# SCH___2022-11-10.net
KiCad netlist of a schematic drawn in EasyEDA
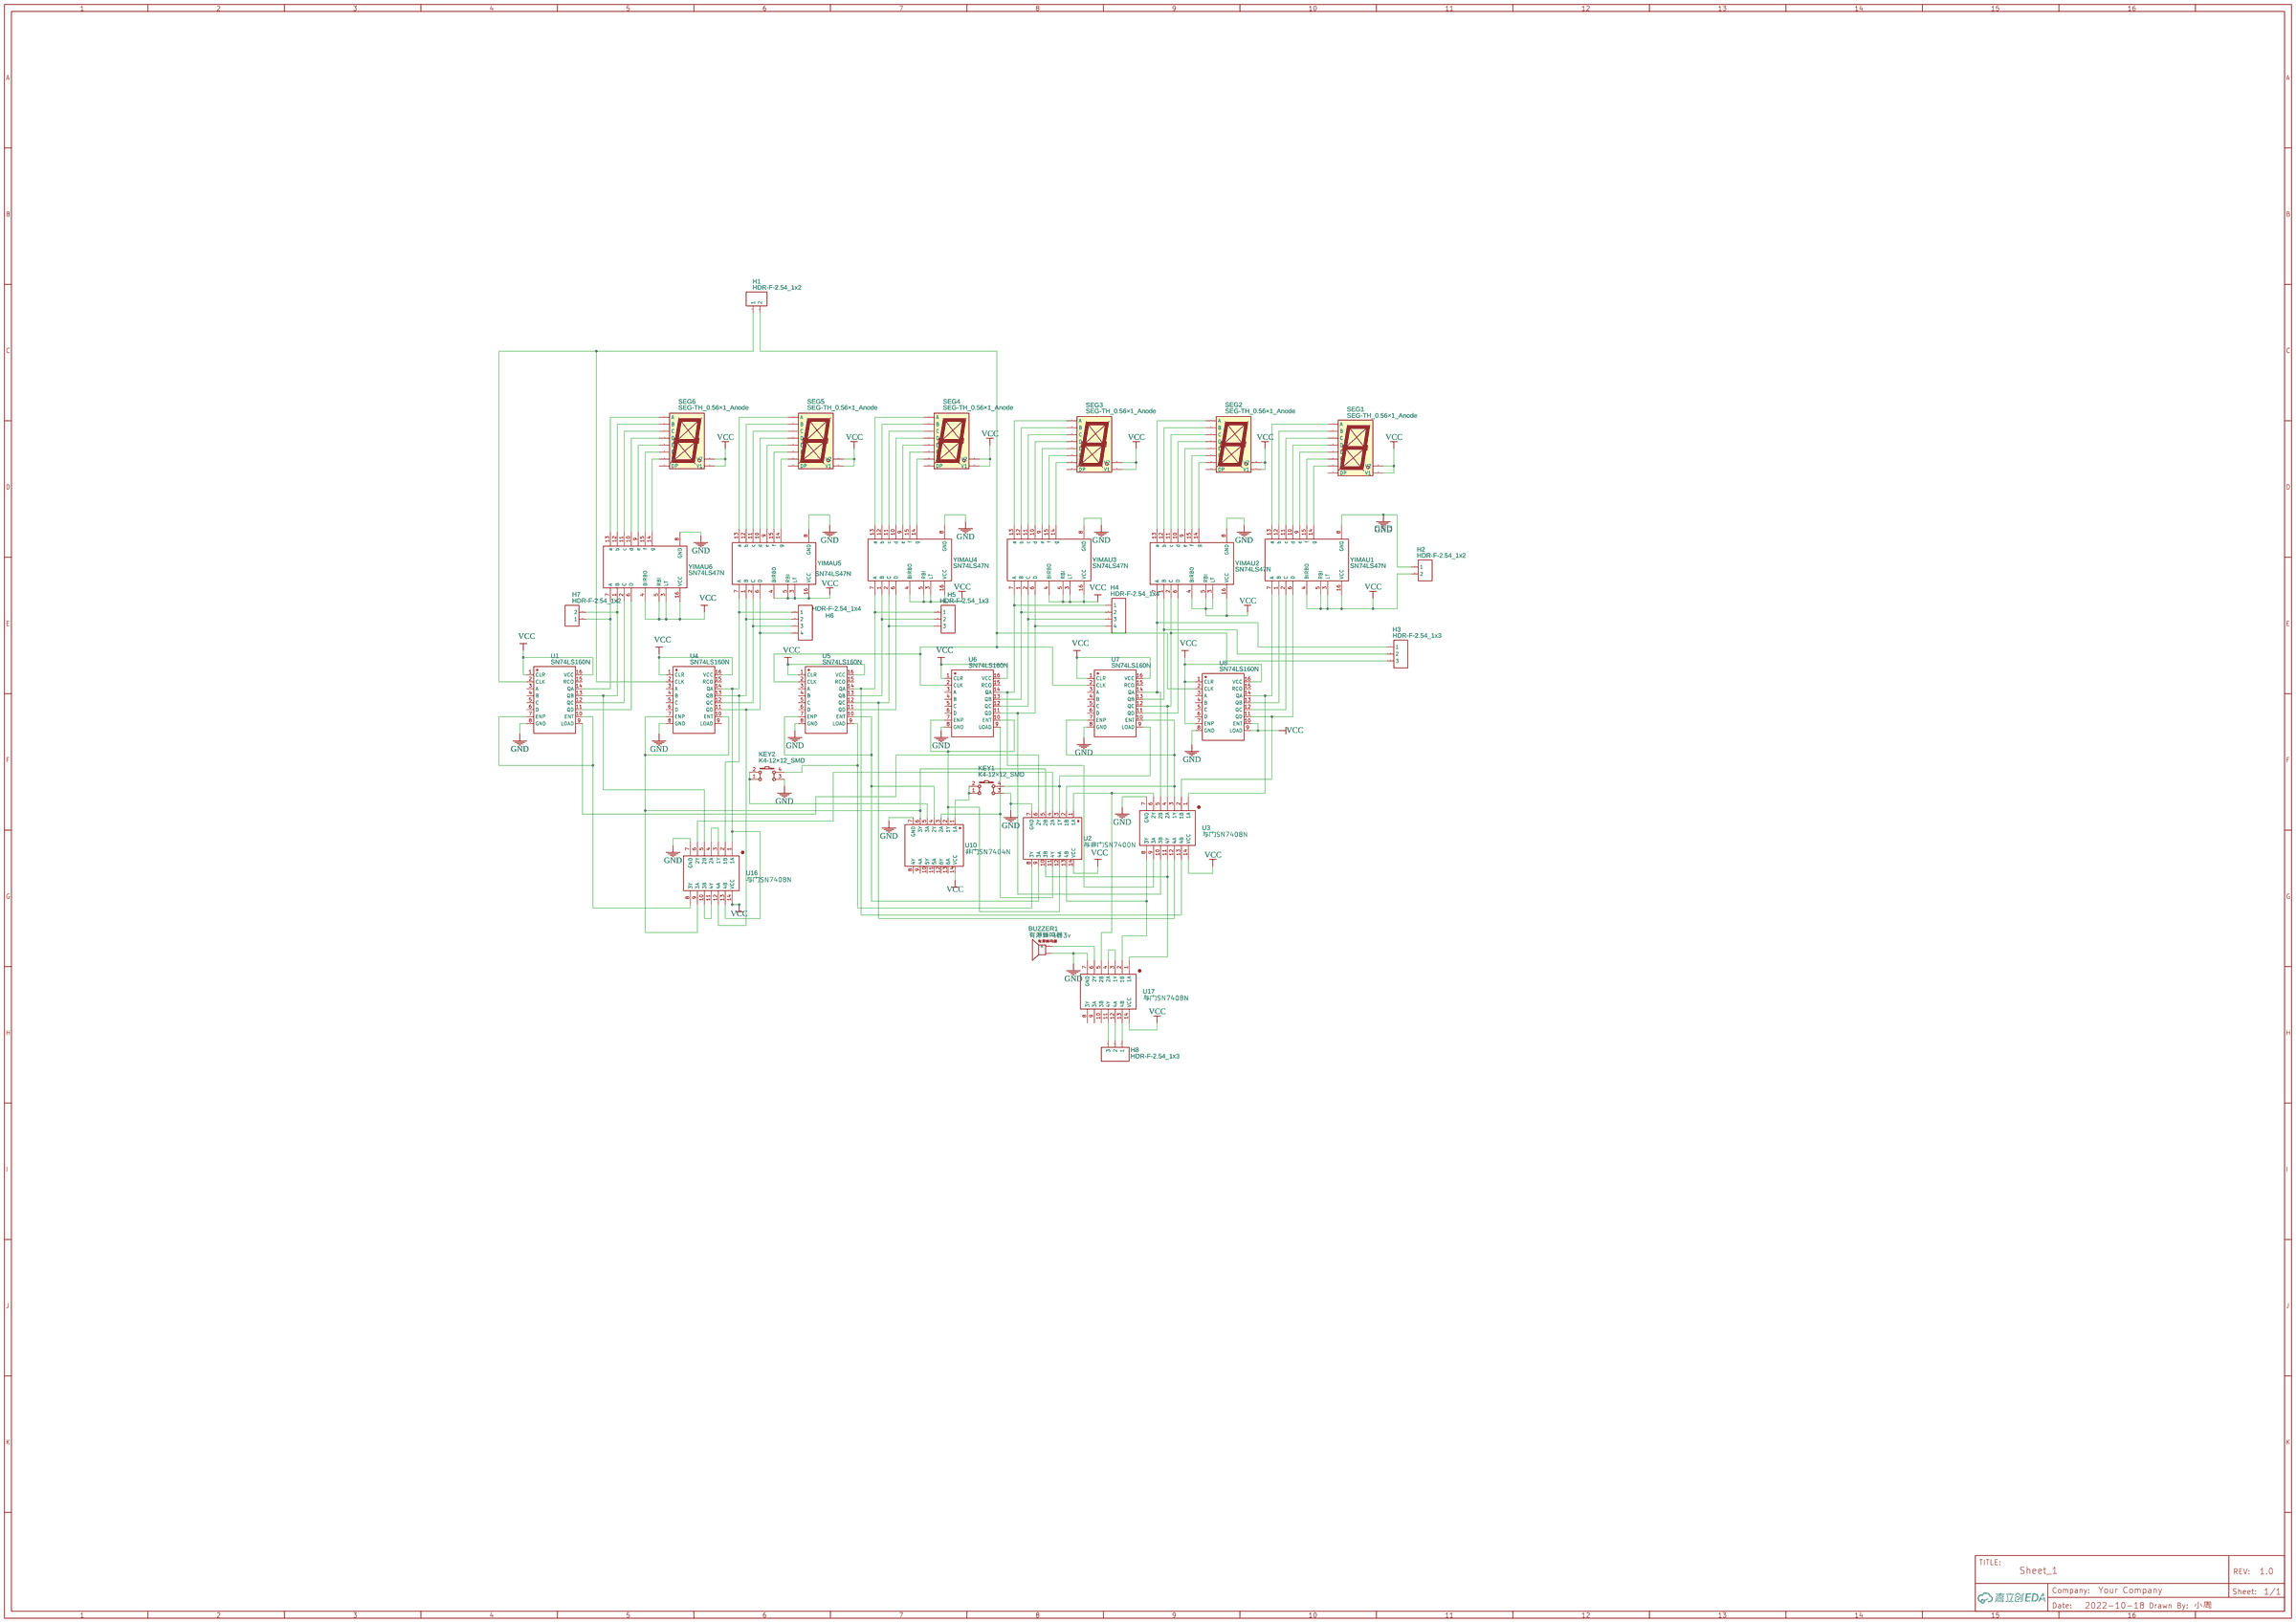
[diagram p0: schematic sheet]

(export (version "E")
  (design (tool "Eeschema 10.0.6"))
  (components
    (comp (ref "BUZZER1")
      (value "有源蜂鸣器3v")
      (fields (field (name "BOM_Manufacturer Part") "TMB12A12") (field (name "BOM_Supplier Part") "C96079"))
      (libsource (lib "") (part "有源蜂鸣器3v"))
    )
    (comp (ref "H1")
      (value "HDR-F-2.54_1x2")
      (fields (field (name "BOM_Supplier Part") "C49661"))
      (libsource (lib "") (part "HDR-F-2.54_1x2"))
    )
    (comp (ref "H2")
      (value "HDR-F-2.54_1x2")
      (fields (field (name "BOM_Supplier Part") "C49661"))
      (libsource (lib "") (part "HDR-F-2.54_1x2_2"))
    )
    (comp (ref "H3")
      (value "HDR-F-2.54_1x3")
      (fields (field (name "BOM_Supplier Part") "C146690"))
      (libsource (lib "") (part "HDR-F-2.54_1x3_1"))
    )
    (comp (ref "H4")
      (value "HDR-F-2.54_1x4")
      (fields (field (name "BOM_Supplier Part") "C225501"))
      (libsource (lib "") (part "HDR-F-2.54_1x4"))
    )
    (comp (ref "H5")
      (value "HDR-F-2.54_1x3")
      (fields (field (name "BOM_Supplier Part") "C146690"))
      (libsource (lib "") (part "HDR-F-2.54_1x3_1"))
    )
    (comp (ref "H6")
      (value "HDR-F-2.54_1x4")
      (fields (field (name "BOM_Supplier Part") "C225501"))
      (libsource (lib "") (part "HDR-F-2.54_1x4"))
    )
    (comp (ref "H7")
      (value "HDR-F-2.54_1x2")
      (fields (field (name "BOM_Supplier Part") "C49661"))
      (libsource (lib "") (part "HDR-F-2.54_1x2_1"))
    )
    (comp (ref "H8")
      (value "HDR-F-2.54_1x3")
      (fields (field (name "BOM_Supplier Part") "C146690"))
      (libsource (lib "") (part "HDR-F-2.54_1x3"))
    )
    (comp (ref "KEY1")
      (value "K4-12×12_SMD")
      (fields
        (field (name "BOM_Manufacturer Part") "K2-1103SP-E4SW-04")
        (field (name "BOM_Supplier Part") "C136697")
      )
      (libsource (lib "") (part "K4-12×12_SMD"))
    )
    (comp (ref "KEY2")
      (value "K4-12×12_SMD")
      (fields
        (field (name "BOM_Manufacturer Part") "K2-1103SP-E4SW-04")
        (field (name "BOM_Supplier Part") "C136697")
      )
      (libsource (lib "") (part "K4-12×12_SMD"))
    )
    (comp (ref "SEG1")
      (value "SEG-TH_0.56×1_Anode")
      (fields (field (name "BOM_Supplier Part") "C8092"))
      (libsource (lib "") (part "SEG-TH_0.56×1_Anode"))
    )
    (comp (ref "SEG2")
      (value "SEG-TH_0.56×1_Anode")
      (fields (field (name "BOM_Supplier Part") "C8092"))
      (libsource (lib "") (part "SEG-TH_0.56×1_Anode"))
    )
    (comp (ref "SEG3")
      (value "SEG-TH_0.56×1_Anode")
      (fields (field (name "BOM_Supplier Part") "C8092"))
      (libsource (lib "") (part "SEG-TH_0.56×1_Anode"))
    )
    (comp (ref "SEG4")
      (value "SEG-TH_0.56×1_Anode")
      (fields (field (name "BOM_Supplier Part") "C8092"))
      (libsource (lib "") (part "SEG-TH_0.56×1_Anode"))
    )
    (comp (ref "SEG5")
      (value "SEG-TH_0.56×1_Anode")
      (fields (field (name "BOM_Supplier Part") "C8092"))
      (libsource (lib "") (part "SEG-TH_0.56×1_Anode"))
    )
    (comp (ref "SEG6")
      (value "SEG-TH_0.56×1_Anode")
      (fields (field (name "BOM_Supplier Part") "C8092"))
      (libsource (lib "") (part "SEG-TH_0.56×1_Anode"))
    )
    (comp (ref "U1")
      (value "SN74LS160N")
      (fields
        (field (name "BOM_Manufacturer Part") "CC0805JRNPO9BN821")
        (field (name "BOM_Supplier Part") "C113834")
      )
      (libsource (lib "") (part "SN74LS160N"))
    )
    (comp (ref "U2") (value "与非门SN7400N") (libsource (lib "") (part "SN7400N")))
    (comp (ref "U3") (value "与门SN7408N") (libsource (lib "") (part "SN7408N")))
    (comp (ref "U4")
      (value "SN74LS160N")
      (fields
        (field (name "BOM_Manufacturer Part") "CC0805JRNPO9BN821")
        (field (name "BOM_Supplier Part") "C113834")
      )
      (libsource (lib "") (part "SN74LS160N"))
    )
    (comp (ref "U5")
      (value "SN74LS160N")
      (fields
        (field (name "BOM_Manufacturer Part") "CC0805JRNPO9BN821")
        (field (name "BOM_Supplier Part") "C113834")
      )
      (libsource (lib "") (part "SN74LS160N"))
    )
    (comp (ref "U6")
      (value "SN74LS160N")
      (fields
        (field (name "BOM_Manufacturer Part") "CC0805JRNPO9BN821")
        (field (name "BOM_Supplier Part") "C113834")
      )
      (libsource (lib "") (part "SN74LS160N"))
    )
    (comp (ref "U7")
      (value "SN74LS160N")
      (fields
        (field (name "BOM_Manufacturer Part") "CC0805JRNPO9BN821")
        (field (name "BOM_Supplier Part") "C113834")
      )
      (libsource (lib "") (part "SN74LS160N"))
    )
    (comp (ref "U8")
      (value "SN74LS160N")
      (fields
        (field (name "BOM_Manufacturer Part") "CC0805JRNPO9BN821")
        (field (name "BOM_Supplier Part") "C113834")
      )
      (libsource (lib "") (part "SN74LS160N"))
    )
    (comp (ref "U10") (value "非门SN7404N") (libsource (lib "") (part "SN7404N")))
    (comp (ref "U16") (value "与门SN7408N") (libsource (lib "") (part "SN7408N")))
    (comp (ref "U17") (value "与门SN7408N") (libsource (lib "") (part "SN7408N")))
    (comp (ref "YIMAU1")
      (value "SN74LS47N")
      (fields (field (name "BOM_Supplier Part") "C129379"))
      (libsource (lib "") (part "Unknown_1870_-1520"))
    )
    (comp (ref "YIMAU2")
      (value "SN74LS47N")
      (fields (field (name "BOM_Supplier Part") "C129379"))
      (libsource (lib "") (part "Unknown_1705_-1515"))
    )
    (comp (ref "YIMAU3")
      (value "SN74LS47N")
      (fields (field (name "BOM_Supplier Part") "C129379"))
      (libsource (lib "") (part "Unknown_1500_-1520"))
    )
    (comp (ref "YIMAU4")
      (value "SN74LS47N")
      (fields (field (name "BOM_Supplier Part") "C129379"))
      (libsource (lib "") (part "Unknown_1300_-1520"))
    )
    (comp (ref "YIMAU5")
      (value "SN74LS47N")
      (fields (field (name "BOM_Supplier Part") "C129379"))
      (libsource (lib "") (part "Unknown_1105_-1515"))
    )
    (comp (ref "YIMAU6")
      (value "SN74LS47N")
      (fields (field (name "BOM_Supplier Part") "C129379"))
      (libsource (lib "") (part "Unknown_920_-1510"))
    )
  )
  (nets
    (net (code "1") (name "GND") (class "Default")
      (node (ref "BUZZER1") (pin "-") (pinfunction "-_-") (pintype "unspecified"))
      (node (ref "H2") (pin "1") (pinfunction "1_1") (pintype "input"))
      (node (ref "KEY1") (pin "3") (pinfunction "3_3") (pintype "unspecified"))
      (node (ref "KEY2") (pin "3") (pinfunction "3_3") (pintype "unspecified"))
      (node (ref "U1") (pin "8") (pinfunction "GND_8") (pintype "unspecified"))
      (node (ref "U10") (pin "7") (pinfunction "GND_7") (pintype "unspecified"))
      (node (ref "U16") (pin "7") (pinfunction "GND_7") (pintype "unspecified"))
      (node (ref "U17") (pin "7") (pinfunction "GND_7") (pintype "unspecified"))
      (node (ref "U2") (pin "7") (pinfunction "GND_7") (pintype "unspecified"))
      (node (ref "U3") (pin "7") (pinfunction "GND_7") (pintype "unspecified"))
      (node (ref "U4") (pin "8") (pinfunction "GND_8") (pintype "unspecified"))
      (node (ref "U5") (pin "8") (pinfunction "GND_8") (pintype "unspecified"))
      (node (ref "U6") (pin "8") (pinfunction "GND_8") (pintype "unspecified"))
      (node (ref "U7") (pin "8") (pinfunction "GND_8") (pintype "unspecified"))
      (node (ref "U8") (pin "8") (pinfunction "GND_8") (pintype "unspecified"))
      (node (ref "YIMAU1") (pin "8") (pinfunction "GND_8") (pintype "passive"))
      (node (ref "YIMAU2") (pin "8") (pinfunction "GND_8") (pintype "passive"))
      (node (ref "YIMAU3") (pin "8") (pinfunction "GND_8") (pintype "passive"))
      (node (ref "YIMAU4") (pin "8") (pinfunction "GND_8") (pintype "passive"))
      (node (ref "YIMAU5") (pin "8") (pinfunction "GND_8") (pintype "passive"))
      (node (ref "YIMAU6") (pin "8") (pinfunction "GND_8") (pintype "passive"))
    )
    (net (code "2") (name "Net-(SEG1-A)") (class "Default")
      (node (ref "SEG1") (pin "7") (pinfunction "A_7") (pintype "unspecified"))
      (node (ref "YIMAU1") (pin "13") (pinfunction "a_13") (pintype "unspecified"))
    )
    (net (code "3") (name "Net-(SEG1-B)") (class "Default")
      (node (ref "SEG1") (pin "6") (pinfunction "B_6") (pintype "unspecified"))
      (node (ref "YIMAU1") (pin "12") (pinfunction "b_12") (pintype "unspecified"))
    )
    (net (code "4") (name "Net-(SEG1-C)") (class "Default")
      (node (ref "SEG1") (pin "4") (pinfunction "C_4") (pintype "unspecified"))
      (node (ref "YIMAU1") (pin "11") (pinfunction "c_11") (pintype "unspecified"))
    )
    (net (code "5") (name "Net-(SEG1-D)") (class "Default")
      (node (ref "SEG1") (pin "2") (pinfunction "D_2") (pintype "unspecified"))
      (node (ref "YIMAU1") (pin "10") (pinfunction "d_10") (pintype "unspecified"))
    )
    (net (code "6") (name "Net-(SEG1-E)") (class "Default")
      (node (ref "SEG1") (pin "1") (pinfunction "E_1") (pintype "unspecified"))
      (node (ref "YIMAU1") (pin "9") (pinfunction "e_9") (pintype "unspecified"))
    )
    (net (code "7") (name "Net-(SEG1-F)") (class "Default")
      (node (ref "SEG1") (pin "9") (pinfunction "F_9") (pintype "unspecified"))
      (node (ref "YIMAU1") (pin "15") (pinfunction "f_15") (pintype "unspecified"))
    )
    (net (code "8") (name "Net-(SEG1-G)") (class "Default")
      (node (ref "SEG1") (pin "10") (pinfunction "G_10") (pintype "unspecified"))
      (node (ref "YIMAU1") (pin "14") (pinfunction "g_14") (pintype "unspecified"))
    )
    (net (code "9") (name "Net-(SEG2-A)") (class "Default")
      (node (ref "SEG2") (pin "7") (pinfunction "A_7") (pintype "unspecified"))
      (node (ref "YIMAU2") (pin "13") (pinfunction "a_13") (pintype "unspecified"))
    )
    (net (code "10") (name "Net-(SEG2-B)") (class "Default")
      (node (ref "SEG2") (pin "6") (pinfunction "B_6") (pintype "unspecified"))
      (node (ref "YIMAU2") (pin "12") (pinfunction "b_12") (pintype "unspecified"))
    )
    (net (code "11") (name "Net-(SEG2-C)") (class "Default")
      (node (ref "SEG2") (pin "4") (pinfunction "C_4") (pintype "unspecified"))
      (node (ref "YIMAU2") (pin "11") (pinfunction "c_11") (pintype "unspecified"))
    )
    (net (code "12") (name "Net-(SEG2-D)") (class "Default")
      (node (ref "SEG2") (pin "2") (pinfunction "D_2") (pintype "unspecified"))
      (node (ref "YIMAU2") (pin "10") (pinfunction "d_10") (pintype "unspecified"))
    )
    (net (code "13") (name "Net-(SEG2-E)") (class "Default")
      (node (ref "SEG2") (pin "1") (pinfunction "E_1") (pintype "unspecified"))
      (node (ref "YIMAU2") (pin "9") (pinfunction "e_9") (pintype "unspecified"))
    )
    (net (code "14") (name "Net-(SEG2-F)") (class "Default")
      (node (ref "SEG2") (pin "9") (pinfunction "F_9") (pintype "unspecified"))
      (node (ref "YIMAU2") (pin "15") (pinfunction "f_15") (pintype "unspecified"))
    )
    (net (code "15") (name "Net-(SEG2-G)") (class "Default")
      (node (ref "SEG2") (pin "10") (pinfunction "G_10") (pintype "unspecified"))
      (node (ref "YIMAU2") (pin "14") (pinfunction "g_14") (pintype "unspecified"))
    )
    (net (code "16") (name "Net-(SEG3-A)") (class "Default")
      (node (ref "SEG3") (pin "7") (pinfunction "A_7") (pintype "unspecified"))
      (node (ref "YIMAU3") (pin "13") (pinfunction "a_13") (pintype "unspecified"))
    )
    (net (code "17") (name "Net-(SEG3-B)") (class "Default")
      (node (ref "SEG3") (pin "6") (pinfunction "B_6") (pintype "unspecified"))
      (node (ref "YIMAU3") (pin "12") (pinfunction "b_12") (pintype "unspecified"))
    )
    (net (code "18") (name "Net-(SEG3-C)") (class "Default")
      (node (ref "SEG3") (pin "4") (pinfunction "C_4") (pintype "unspecified"))
      (node (ref "YIMAU3") (pin "11") (pinfunction "c_11") (pintype "unspecified"))
    )
    (net (code "19") (name "Net-(SEG3-D)") (class "Default")
      (node (ref "SEG3") (pin "2") (pinfunction "D_2") (pintype "unspecified"))
      (node (ref "YIMAU3") (pin "10") (pinfunction "d_10") (pintype "unspecified"))
    )
    (net (code "20") (name "Net-(SEG3-E)") (class "Default")
      (node (ref "SEG3") (pin "1") (pinfunction "E_1") (pintype "unspecified"))
      (node (ref "YIMAU3") (pin "9") (pinfunction "e_9") (pintype "unspecified"))
    )
    (net (code "21") (name "Net-(SEG3-F)") (class "Default")
      (node (ref "SEG3") (pin "9") (pinfunction "F_9") (pintype "unspecified"))
      (node (ref "YIMAU3") (pin "15") (pinfunction "f_15") (pintype "unspecified"))
    )
    (net (code "22") (name "Net-(SEG3-G)") (class "Default")
      (node (ref "SEG3") (pin "10") (pinfunction "G_10") (pintype "unspecified"))
      (node (ref "YIMAU3") (pin "14") (pinfunction "g_14") (pintype "unspecified"))
    )
    (net (code "23") (name "Net-(SEG4-A)") (class "Default")
      (node (ref "SEG4") (pin "7") (pinfunction "A_7") (pintype "unspecified"))
      (node (ref "YIMAU4") (pin "13") (pinfunction "a_13") (pintype "unspecified"))
    )
    (net (code "24") (name "Net-(SEG4-B)") (class "Default")
      (node (ref "SEG4") (pin "6") (pinfunction "B_6") (pintype "unspecified"))
      (node (ref "YIMAU4") (pin "12") (pinfunction "b_12") (pintype "unspecified"))
    )
    (net (code "25") (name "Net-(SEG4-C)") (class "Default")
      (node (ref "SEG4") (pin "4") (pinfunction "C_4") (pintype "unspecified"))
      (node (ref "YIMAU4") (pin "11") (pinfunction "c_11") (pintype "unspecified"))
    )
    (net (code "26") (name "Net-(SEG4-D)") (class "Default")
      (node (ref "SEG4") (pin "2") (pinfunction "D_2") (pintype "unspecified"))
      (node (ref "YIMAU4") (pin "10") (pinfunction "d_10") (pintype "unspecified"))
    )
    (net (code "27") (name "Net-(SEG4-E)") (class "Default")
      (node (ref "SEG4") (pin "1") (pinfunction "E_1") (pintype "unspecified"))
      (node (ref "YIMAU4") (pin "9") (pinfunction "e_9") (pintype "unspecified"))
    )
    (net (code "28") (name "Net-(SEG4-F)") (class "Default")
      (node (ref "SEG4") (pin "9") (pinfunction "F_9") (pintype "unspecified"))
      (node (ref "YIMAU4") (pin "15") (pinfunction "f_15") (pintype "unspecified"))
    )
    (net (code "29") (name "Net-(SEG4-G)") (class "Default")
      (node (ref "SEG4") (pin "10") (pinfunction "G_10") (pintype "unspecified"))
      (node (ref "YIMAU4") (pin "14") (pinfunction "g_14") (pintype "unspecified"))
    )
    (net (code "30") (name "Net-(SEG5-A)") (class "Default")
      (node (ref "SEG5") (pin "7") (pinfunction "A_7") (pintype "unspecified"))
      (node (ref "YIMAU5") (pin "13") (pinfunction "a_13") (pintype "unspecified"))
    )
    (net (code "31") (name "Net-(SEG5-B)") (class "Default")
      (node (ref "SEG5") (pin "6") (pinfunction "B_6") (pintype "unspecified"))
      (node (ref "YIMAU5") (pin "12") (pinfunction "b_12") (pintype "unspecified"))
    )
    (net (code "32") (name "Net-(SEG5-C)") (class "Default")
      (node (ref "SEG5") (pin "4") (pinfunction "C_4") (pintype "unspecified"))
      (node (ref "YIMAU5") (pin "11") (pinfunction "c_11") (pintype "unspecified"))
    )
    (net (code "33") (name "Net-(SEG5-D)") (class "Default")
      (node (ref "SEG5") (pin "2") (pinfunction "D_2") (pintype "unspecified"))
      (node (ref "YIMAU5") (pin "10") (pinfunction "d_10") (pintype "unspecified"))
    )
    (net (code "34") (name "Net-(SEG5-E)") (class "Default")
      (node (ref "SEG5") (pin "1") (pinfunction "E_1") (pintype "unspecified"))
      (node (ref "YIMAU5") (pin "9") (pinfunction "e_9") (pintype "unspecified"))
    )
    (net (code "35") (name "Net-(SEG5-F)") (class "Default")
      (node (ref "SEG5") (pin "9") (pinfunction "F_9") (pintype "unspecified"))
      (node (ref "YIMAU5") (pin "15") (pinfunction "f_15") (pintype "unspecified"))
    )
    (net (code "36") (name "Net-(SEG5-G)") (class "Default")
      (node (ref "SEG5") (pin "10") (pinfunction "G_10") (pintype "unspecified"))
      (node (ref "YIMAU5") (pin "14") (pinfunction "g_14") (pintype "unspecified"))
    )
    (net (code "37") (name "Net-(SEG6-A)") (class "Default")
      (node (ref "SEG6") (pin "7") (pinfunction "A_7") (pintype "unspecified"))
      (node (ref "YIMAU6") (pin "13") (pinfunction "a_13") (pintype "unspecified"))
    )
    (net (code "38") (name "Net-(SEG6-B)") (class "Default")
      (node (ref "SEG6") (pin "6") (pinfunction "B_6") (pintype "unspecified"))
      (node (ref "YIMAU6") (pin "12") (pinfunction "b_12") (pintype "unspecified"))
    )
    (net (code "39") (name "Net-(SEG6-C)") (class "Default")
      (node (ref "SEG6") (pin "4") (pinfunction "C_4") (pintype "unspecified"))
      (node (ref "YIMAU6") (pin "11") (pinfunction "c_11") (pintype "unspecified"))
    )
    (net (code "40") (name "Net-(SEG6-D)") (class "Default")
      (node (ref "SEG6") (pin "2") (pinfunction "D_2") (pintype "unspecified"))
      (node (ref "YIMAU6") (pin "10") (pinfunction "d_10") (pintype "unspecified"))
    )
    (net (code "41") (name "Net-(SEG6-E)") (class "Default")
      (node (ref "SEG6") (pin "1") (pinfunction "E_1") (pintype "unspecified"))
      (node (ref "YIMAU6") (pin "9") (pinfunction "e_9") (pintype "unspecified"))
    )
    (net (code "42") (name "Net-(SEG6-F)") (class "Default")
      (node (ref "SEG6") (pin "9") (pinfunction "F_9") (pintype "unspecified"))
      (node (ref "YIMAU6") (pin "15") (pinfunction "f_15") (pintype "unspecified"))
    )
    (net (code "43") (name "Net-(SEG6-G)") (class "Default")
      (node (ref "SEG6") (pin "10") (pinfunction "G_10") (pintype "unspecified"))
      (node (ref "YIMAU6") (pin "14") (pinfunction "g_14") (pintype "unspecified"))
    )
    (net (code "44") (name "Net-(U1-CLK)") (class "Default")
      (node (ref "H1") (pin "1") (pinfunction "1_1") (pintype "input"))
      (node (ref "U1") (pin "2") (pinfunction "CLK_2") (pintype "unspecified"))
      (node (ref "U4") (pin "2") (pinfunction "CLK_2") (pintype "unspecified"))
    )
    (net (code "45") (name "Net-(U1-ENP)") (class "Default")
      (node (ref "U1") (pin "10") (pinfunction "ENT_10") (pintype "unspecified"))
      (node (ref "U1") (pin "7") (pinfunction "ENP_7") (pintype "unspecified"))
      (node (ref "U16") (pin "8") (pinfunction "3Y_8") (pintype "unspecified"))
    )
    (net (code "46") (name "Net-(U1-LOAD)") (class "Default")
      (node (ref "U1") (pin "9") (pinfunction "LOAD_9") (pintype "unspecified"))
      (node (ref "U2") (pin "6") (pinfunction "2Y_6") (pintype "unspecified"))
    )
    (net (code "47") (name "Net-(U1-QA)") (class "Default")
      (node (ref "H7") (pin "1") (pinfunction "1_1") (pintype "input"))
      (node (ref "U1") (pin "14") (pinfunction "QA_14") (pintype "unspecified"))
      (node (ref "YIMAU6") (pin "7") (pinfunction "A_7") (pintype "unspecified"))
    )
    (net (code "48") (name "Net-(U1-QB)") (class "Default")
      (node (ref "H7") (pin "2") (pinfunction "2_2") (pintype "input"))
      (node (ref "U1") (pin "13") (pinfunction "QB_13") (pintype "unspecified"))
      (node (ref "U16") (pin "5") (pinfunction "2B_5") (pintype "unspecified"))
      (node (ref "YIMAU6") (pin "1") (pinfunction "B_1") (pintype "unspecified"))
    )
    (net (code "49") (name "Net-(U1-QC)") (class "Default")
      (node (ref "U1") (pin "12") (pinfunction "QC_12") (pintype "unspecified"))
      (node (ref "YIMAU6") (pin "2") (pinfunction "C_2") (pintype "unspecified"))
    )
    (net (code "50") (name "Net-(U1-QD)") (class "Default")
      (node (ref "U1") (pin "11") (pinfunction "QD_11") (pintype "unspecified"))
      (node (ref "YIMAU6") (pin "6") (pinfunction "D_6") (pintype "unspecified"))
    )
    (net (code "51") (name "Net-(U2-1B)") (class "Default")
      (node (ref "U2") (pin "2") (pinfunction "1B_2") (pintype "unspecified"))
      (node (ref "U3") (pin "3") (pinfunction "1Y_3") (pintype "unspecified"))
      (node (ref "U7") (pin "10") (pinfunction "ENT_10") (pintype "unspecified"))
      (node (ref "U7") (pin "7") (pinfunction "ENP_7") (pintype "unspecified"))
    )
    (net (code "52") (name "Net-(U2-1Y)") (class "Default")
      (node (ref "KEY1") (pin "4") (pinfunction "4_4") (pintype "unspecified"))
      (node (ref "U2") (pin "3") (pinfunction "1Y_3") (pintype "unspecified"))
      (node (ref "U7") (pin "9") (pinfunction "LOAD_9") (pintype "unspecified"))
    )
    (net (code "53") (name "Net-(U2-3Y)") (class "Default")
      (node (ref "KEY2") (pin "4") (pinfunction "4_4") (pintype "unspecified"))
      (node (ref "U2") (pin "8") (pinfunction "3Y_8") (pintype "unspecified"))
      (node (ref "U5") (pin "9") (pinfunction "LOAD_9") (pintype "unspecified"))
    )
    (net (code "54") (name "Net-(U3-1A)") (class "Default")
      (node (ref "U3") (pin "1") (pinfunction "1A_1") (pintype "unspecified"))
      (node (ref "U8") (pin "14") (pinfunction "QA_14") (pintype "unspecified"))
      (node (ref "YIMAU1") (pin "7") (pinfunction "A_7") (pintype "unspecified"))
    )
    (net (code "55") (name "Net-(U3-1B)") (class "Default")
      (node (ref "U3") (pin "2") (pinfunction "1B_2") (pintype "unspecified"))
      (node (ref "U8") (pin "11") (pinfunction "QD_11") (pintype "unspecified"))
      (node (ref "YIMAU1") (pin "6") (pinfunction "D_6") (pintype "unspecified"))
    )
    (net (code "56") (name "Net-(U3-2A)") (class "Default")
      (node (ref "H3") (pin "3") (pinfunction "3_3") (pintype "input"))
      (node (ref "U3") (pin "4") (pinfunction "2A_4") (pintype "unspecified"))
      (node (ref "U7") (pin "12") (pinfunction "QC_12") (pintype "unspecified"))
      (node (ref "YIMAU2") (pin "2") (pinfunction "C_2") (pintype "unspecified"))
    )
    (net (code "57") (name "Net-(U3-2B)") (class "Default")
      (node (ref "H3") (pin "1") (pinfunction "1_1") (pintype "input"))
      (node (ref "U3") (pin "5") (pinfunction "2B_5") (pintype "unspecified"))
      (node (ref "U7") (pin "14") (pinfunction "QA_14") (pintype "unspecified"))
      (node (ref "YIMAU2") (pin "7") (pinfunction "A_7") (pintype "unspecified"))
    )
    (net (code "58") (name "Net-(U3-3A)") (class "Default")
      (node (ref "H4") (pin "1") (pinfunction "1_1") (pintype "unspecified"))
      (node (ref "U3") (pin "9") (pinfunction "3A_9") (pintype "unspecified"))
      (node (ref "U6") (pin "14") (pinfunction "QA_14") (pintype "unspecified"))
      (node (ref "YIMAU3") (pin "7") (pinfunction "A_7") (pintype "unspecified"))
    )
    (net (code "59") (name "Net-(U3-3B)") (class "Default")
      (node (ref "H4") (pin "4") (pinfunction "4_4") (pintype "unspecified"))
      (node (ref "U3") (pin "10") (pinfunction "3B_10") (pintype "unspecified"))
      (node (ref "U6") (pin "11") (pinfunction "QD_11") (pintype "unspecified"))
      (node (ref "YIMAU3") (pin "6") (pinfunction "D_6") (pintype "unspecified"))
    )
    (net (code "60") (name "Net-(U3-4A)") (class "Default")
      (node (ref "H5") (pin "3") (pinfunction "3_3") (pintype "input"))
      (node (ref "U3") (pin "12") (pinfunction "4A_12") (pintype "unspecified"))
      (node (ref "U5") (pin "12") (pinfunction "QC_12") (pintype "unspecified"))
      (node (ref "YIMAU4") (pin "2") (pinfunction "C_2") (pintype "unspecified"))
    )
    (net (code "61") (name "Net-(U3-4B)") (class "Default")
      (node (ref "H5") (pin "1") (pinfunction "1_1") (pintype "input"))
      (node (ref "U3") (pin "13") (pinfunction "4B_13") (pintype "unspecified"))
      (node (ref "U5") (pin "14") (pinfunction "QA_14") (pintype "unspecified"))
      (node (ref "YIMAU4") (pin "7") (pinfunction "A_7") (pintype "unspecified"))
    )
    (net (code "62") (name "Net-(U4-QC)") (class "Default")
      (node (ref "H6") (pin "3") (pinfunction "3_3") (pintype "unspecified"))
      (node (ref "U4") (pin "12") (pinfunction "QC_12") (pintype "unspecified"))
      (node (ref "YIMAU5") (pin "2") (pinfunction "C_2") (pintype "unspecified"))
    )
    (net (code "63") (name "Net-(U5-CLK)") (class "Default")
      (node (ref "H1") (pin "2") (pinfunction "2_2") (pintype "input"))
      (node (ref "U5") (pin "2") (pinfunction "CLK_2") (pintype "unspecified"))
      (node (ref "U6") (pin "2") (pinfunction "CLK_2") (pintype "unspecified"))
      (node (ref "U7") (pin "2") (pinfunction "CLK_2") (pintype "unspecified"))
      (node (ref "U8") (pin "2") (pinfunction "CLK_2") (pintype "unspecified"))
    )
    (net (code "64") (name "Net-(U5-QB)") (class "Default")
      (node (ref "H5") (pin "2") (pinfunction "2_2") (pintype "input"))
      (node (ref "U5") (pin "13") (pinfunction "QB_13") (pintype "unspecified"))
      (node (ref "YIMAU4") (pin "1") (pinfunction "B_1") (pintype "unspecified"))
    )
    (net (code "65") (name "Net-(U5-QD)") (class "Default")
      (node (ref "U5") (pin "11") (pinfunction "QD_11") (pintype "unspecified"))
      (node (ref "YIMAU4") (pin "6") (pinfunction "D_6") (pintype "unspecified"))
    )
    (net (code "66") (name "Net-(U6-QB)") (class "Default")
      (node (ref "H4") (pin "2") (pinfunction "2_2") (pintype "unspecified"))
      (node (ref "U6") (pin "13") (pinfunction "QB_13") (pintype "unspecified"))
      (node (ref "YIMAU3") (pin "1") (pinfunction "B_1") (pintype "unspecified"))
    )
    (net (code "67") (name "Net-(U6-QC)") (class "Default")
      (node (ref "H4") (pin "3") (pinfunction "3_3") (pintype "unspecified"))
      (node (ref "U6") (pin "12") (pinfunction "QC_12") (pintype "unspecified"))
      (node (ref "YIMAU3") (pin "2") (pinfunction "C_2") (pintype "unspecified"))
    )
    (net (code "68") (name "Net-(U7-QB)") (class "Default")
      (node (ref "H3") (pin "2") (pinfunction "2_2") (pintype "input"))
      (node (ref "U7") (pin "13") (pinfunction "QB_13") (pintype "unspecified"))
      (node (ref "YIMAU2") (pin "1") (pinfunction "B_1") (pintype "unspecified"))
    )
    (net (code "69") (name "Net-(U7-QD)") (class "Default")
      (node (ref "U7") (pin "11") (pinfunction "QD_11") (pintype "unspecified"))
      (node (ref "YIMAU2") (pin "6") (pinfunction "D_6") (pintype "unspecified"))
    )
    (net (code "70") (name "Net-(U8-QB)") (class "Default")
      (node (ref "U8") (pin "13") (pinfunction "QB_13") (pintype "unspecified"))
      (node (ref "YIMAU1") (pin "1") (pinfunction "B_1") (pintype "unspecified"))
    )
    (net (code "71") (name "Net-(U8-QC)") (class "Default")
      (node (ref "U8") (pin "12") (pinfunction "QC_12") (pintype "unspecified"))
      (node (ref "YIMAU1") (pin "2") (pinfunction "C_2") (pintype "unspecified"))
    )
    (net (code "72") (name "Net-(U10-1A)") (class "Default")
      (node (ref "KEY1") (pin "1") (pinfunction "1_1") (pintype "unspecified"))
      (node (ref "KEY1") (pin "2") (pinfunction "2_2") (pintype "unspecified"))
      (node (ref "U10") (pin "1") (pinfunction "1A_1") (pintype "unspecified"))
    )
    (net (code "73") (name "Net-(U10-1Y)") (class "Default")
      (node (ref "U10") (pin "2") (pinfunction "1Y_2") (pintype "unspecified"))
      (node (ref "U2") (pin "12") (pinfunction "4A_12") (pintype "unspecified"))
      (node (ref "U6") (pin "10") (pinfunction "ENT_10") (pintype "unspecified"))
      (node (ref "U6") (pin "7") (pinfunction "ENP_7") (pintype "unspecified"))
    )
    (net (code "74") (name "Net-(U10-2A)") (class "Default")
      (node (ref "U10") (pin "3") (pinfunction "2A_3") (pintype "unspecified"))
      (node (ref "U2") (pin "11") (pinfunction "4Y_11") (pintype "unspecified"))
      (node (ref "U6") (pin "9") (pinfunction "LOAD_9") (pintype "unspecified"))
    )
    (net (code "75") (name "Net-(U10-2Y)") (class "Default")
      (node (ref "U10") (pin "4") (pinfunction "2Y_4") (pintype "unspecified"))
      (node (ref "U2") (pin "9") (pinfunction "3A_9") (pintype "unspecified"))
      (node (ref "U5") (pin "10") (pinfunction "ENT_10") (pintype "unspecified"))
      (node (ref "U5") (pin "7") (pinfunction "ENP_7") (pintype "unspecified"))
    )
    (net (code "76") (name "Net-(U10-3A)") (class "Default")
      (node (ref "KEY2") (pin "1") (pinfunction "1_1") (pintype "unspecified"))
      (node (ref "KEY2") (pin "2") (pinfunction "2_2") (pintype "unspecified"))
      (node (ref "U10") (pin "5") (pinfunction "3A_5") (pintype "unspecified"))
    )
    (net (code "77") (name "Net-(U10-3Y)") (class "Default")
      (node (ref "U10") (pin "6") (pinfunction "3Y_6") (pintype "unspecified"))
      (node (ref "U16") (pin "9") (pinfunction "3A_9") (pintype "unspecified"))
      (node (ref "U2") (pin "5") (pinfunction "2B_5") (pintype "unspecified"))
      (node (ref "U4") (pin "10") (pinfunction "ENT_10") (pintype "unspecified"))
      (node (ref "U4") (pin "7") (pinfunction "ENP_7") (pintype "unspecified"))
    )
    (net (code "78") (name "Net-(U16-1A)") (class "Default")
      (node (ref "H6") (pin "1") (pinfunction "1_1") (pintype "unspecified"))
      (node (ref "U16") (pin "1") (pinfunction "1A_1") (pintype "unspecified"))
      (node (ref "U16") (pin "13") (pinfunction "4B_13") (pintype "unspecified"))
      (node (ref "U4") (pin "14") (pinfunction "QA_14") (pintype "unspecified"))
      (node (ref "YIMAU5") (pin "7") (pinfunction "A_7") (pintype "unspecified"))
    )
    (net (code "79") (name "Net-(U16-1B)") (class "Default")
      (node (ref "H6") (pin "2") (pinfunction "2_2") (pintype "unspecified"))
      (node (ref "U16") (pin "2") (pinfunction "1B_2") (pintype "unspecified"))
      (node (ref "U4") (pin "13") (pinfunction "QB_13") (pintype "unspecified"))
      (node (ref "YIMAU5") (pin "1") (pinfunction "B_1") (pintype "unspecified"))
    )
    (net (code "80") (name "Net-(U16-1Y)") (class "Default")
      (node (ref "U16") (pin "3") (pinfunction "1Y_3") (pintype "unspecified"))
      (node (ref "U16") (pin "4") (pinfunction "2A_4") (pintype "unspecified"))
    )
    (net (code "81") (name "Net-(U16-2Y)") (class "Default")
      (node (ref "U16") (pin "6") (pinfunction "2Y_6") (pintype "unspecified"))
      (node (ref "U2") (pin "4") (pinfunction "2A_4") (pintype "unspecified"))
    )
    (net (code "82") (name "Net-(U16-3B)") (class "Default")
      (node (ref "U16") (pin "10") (pinfunction "3B_10") (pintype "unspecified"))
      (node (ref "U16") (pin "11") (pinfunction "4Y_11") (pintype "unspecified"))
    )
    (net (code "83") (name "Net-(U16-4A)") (class "Default")
      (node (ref "H6") (pin "4") (pinfunction "4_4") (pintype "unspecified"))
      (node (ref "U16") (pin "12") (pinfunction "4A_12") (pintype "unspecified"))
      (node (ref "U4") (pin "11") (pinfunction "QD_11") (pintype "unspecified"))
      (node (ref "YIMAU5") (pin "6") (pinfunction "D_6") (pintype "unspecified"))
    )
    (net (code "84") (name "Net-(U17-1A)") (class "Default")
      (node (ref "U17") (pin "1") (pinfunction "1A_1") (pintype "unspecified"))
      (node (ref "U2") (pin "10") (pinfunction "3B_10") (pintype "unspecified"))
      (node (ref "U3") (pin "11") (pinfunction "4Y_11") (pintype "unspecified"))
    )
    (net (code "85") (name "Net-(U17-1B)") (class "Default")
      (node (ref "U17") (pin "2") (pinfunction "1B_2") (pintype "unspecified"))
      (node (ref "U2") (pin "13") (pinfunction "4B_13") (pintype "unspecified"))
      (node (ref "U3") (pin "8") (pinfunction "3Y_8") (pintype "unspecified"))
    )
    (net (code "86") (name "Net-(U17-1Y)") (class "Default")
      (node (ref "U17") (pin "3") (pinfunction "1Y_3") (pintype "unspecified"))
      (node (ref "U17") (pin "4") (pinfunction "2A_4") (pintype "unspecified"))
    )
    (net (code "87") (name "Net-(U17-2B)") (class "Default")
      (node (ref "U17") (pin "5") (pinfunction "2B_5") (pintype "unspecified"))
      (node (ref "U2") (pin "1") (pinfunction "1A_1") (pintype "unspecified"))
      (node (ref "U3") (pin "6") (pinfunction "2Y_6") (pintype "unspecified"))
    )
    (net (code "88") (name "Net-(U17-2Y)") (class "Default")
      (node (ref "BUZZER1") (pin "+") (pinfunction "+_+") (pintype "unspecified"))
      (node (ref "U17") (pin "6") (pinfunction "2Y_6") (pintype "unspecified"))
    )
    (net (code "89") (name "Net-(U17-4A)") (class "Default")
      (node (ref "H8") (pin "2") (pinfunction "2_2") (pintype "input"))
      (node (ref "U17") (pin "12") (pinfunction "4A_12") (pintype "unspecified"))
    )
    (net (code "90") (name "Net-(U17-4B)") (class "Default")
      (node (ref "H8") (pin "1") (pinfunction "1_1") (pintype "input"))
      (node (ref "U17") (pin "13") (pinfunction "4B_13") (pintype "unspecified"))
    )
    (net (code "91") (name "Net-(U17-4Y)") (class "Default")
      (node (ref "H8") (pin "3") (pinfunction "3_3") (pintype "input"))
      (node (ref "U17") (pin "11") (pinfunction "4Y_11") (pintype "unspecified"))
    )
    (net (code "92") (name "VCC") (class "Default")
      (node (ref "H2") (pin "2") (pinfunction "2_2") (pintype "input"))
      (node (ref "SEG1") (pin "3") (pinfunction "V1_3") (pintype "unspecified"))
      (node (ref "SEG1") (pin "8") (pinfunction "V2_8") (pintype "unspecified"))
      (node (ref "SEG2") (pin "3") (pinfunction "V1_3") (pintype "unspecified"))
      (node (ref "SEG2") (pin "8") (pinfunction "V2_8") (pintype "unspecified"))
      (node (ref "SEG3") (pin "3") (pinfunction "V1_3") (pintype "unspecified"))
      (node (ref "SEG3") (pin "8") (pinfunction "V2_8") (pintype "unspecified"))
      (node (ref "SEG4") (pin "3") (pinfunction "V1_3") (pintype "unspecified"))
      (node (ref "SEG4") (pin "8") (pinfunction "V2_8") (pintype "unspecified"))
      (node (ref "SEG5") (pin "3") (pinfunction "V1_3") (pintype "unspecified"))
      (node (ref "SEG5") (pin "8") (pinfunction "V2_8") (pintype "unspecified"))
      (node (ref "SEG6") (pin "3") (pinfunction "V1_3") (pintype "unspecified"))
      (node (ref "SEG6") (pin "8") (pinfunction "V2_8") (pintype "unspecified"))
      (node (ref "U1") (pin "1") (pinfunction "CLR_1") (pintype "unspecified"))
      (node (ref "U1") (pin "16") (pinfunction "VCC_16") (pintype "unspecified"))
      (node (ref "U10") (pin "14") (pinfunction "VCC_14") (pintype "unspecified"))
      (node (ref "U16") (pin "14") (pinfunction "VCC_14") (pintype "unspecified"))
      (node (ref "U17") (pin "14") (pinfunction "VCC_14") (pintype "unspecified"))
      (node (ref "U2") (pin "14") (pinfunction "VCC_14") (pintype "unspecified"))
      (node (ref "U3") (pin "14") (pinfunction "VCC_14") (pintype "unspecified"))
      (node (ref "U4") (pin "1") (pinfunction "CLR_1") (pintype "unspecified"))
      (node (ref "U4") (pin "16") (pinfunction "VCC_16") (pintype "unspecified"))
      (node (ref "U5") (pin "1") (pinfunction "CLR_1") (pintype "unspecified"))
      (node (ref "U5") (pin "16") (pinfunction "VCC_16") (pintype "unspecified"))
      (node (ref "U6") (pin "1") (pinfunction "CLR_1") (pintype "unspecified"))
      (node (ref "U6") (pin "16") (pinfunction "VCC_16") (pintype "unspecified"))
      (node (ref "U7") (pin "1") (pinfunction "CLR_1") (pintype "unspecified"))
      (node (ref "U7") (pin "16") (pinfunction "VCC_16") (pintype "unspecified"))
      (node (ref "U8") (pin "1") (pinfunction "CLR_1") (pintype "unspecified"))
      (node (ref "U8") (pin "10") (pinfunction "ENT_10") (pintype "unspecified"))
      (node (ref "U8") (pin "16") (pinfunction "VCC_16") (pintype "unspecified"))
      (node (ref "U8") (pin "7") (pinfunction "ENP_7") (pintype "unspecified"))
      (node (ref "U8") (pin "9") (pinfunction "LOAD_9") (pintype "unspecified"))
      (node (ref "YIMAU1") (pin "16") (pinfunction "VCC_16") (pintype "passive"))
      (node (ref "YIMAU1") (pin "3") (pinfunction "LT_3") (pintype "unspecified"))
      (node (ref "YIMAU1") (pin "4") (pinfunction "BIRBO_4") (pintype "bidirectional"))
      (node (ref "YIMAU1") (pin "5") (pinfunction "RBI_5") (pintype "unspecified"))
      (node (ref "YIMAU2") (pin "16") (pinfunction "VCC_16") (pintype "passive"))
      (node (ref "YIMAU2") (pin "3") (pinfunction "LT_3") (pintype "unspecified"))
      (node (ref "YIMAU2") (pin "4") (pinfunction "BIRBO_4") (pintype "bidirectional"))
      (node (ref "YIMAU2") (pin "5") (pinfunction "RBI_5") (pintype "unspecified"))
      (node (ref "YIMAU3") (pin "16") (pinfunction "VCC_16") (pintype "passive"))
      (node (ref "YIMAU3") (pin "3") (pinfunction "LT_3") (pintype "unspecified"))
      (node (ref "YIMAU3") (pin "4") (pinfunction "BIRBO_4") (pintype "bidirectional"))
      (node (ref "YIMAU3") (pin "5") (pinfunction "RBI_5") (pintype "unspecified"))
      (node (ref "YIMAU4") (pin "16") (pinfunction "VCC_16") (pintype "passive"))
      (node (ref "YIMAU4") (pin "3") (pinfunction "LT_3") (pintype "unspecified"))
      (node (ref "YIMAU4") (pin "4") (pinfunction "BIRBO_4") (pintype "bidirectional"))
      (node (ref "YIMAU4") (pin "5") (pinfunction "RBI_5") (pintype "unspecified"))
      (node (ref "YIMAU5") (pin "16") (pinfunction "VCC_16") (pintype "passive"))
      (node (ref "YIMAU5") (pin "3") (pinfunction "LT_3") (pintype "unspecified"))
      (node (ref "YIMAU5") (pin "4") (pinfunction "BIRBO_4") (pintype "bidirectional"))
      (node (ref "YIMAU5") (pin "5") (pinfunction "RBI_5") (pintype "unspecified"))
      (node (ref "YIMAU6") (pin "16") (pinfunction "VCC_16") (pintype "passive"))
      (node (ref "YIMAU6") (pin "3") (pinfunction "LT_3") (pintype "unspecified"))
      (node (ref "YIMAU6") (pin "4") (pinfunction "BIRBO_4") (pintype "bidirectional"))
      (node (ref "YIMAU6") (pin "5") (pinfunction "RBI_5") (pintype "unspecified"))
    )
    (net (code "93") (name "unconnected-(SEG1-DP-Pad5)") (class "Default")
      (node (ref "SEG1") (pin "5") (pinfunction "DP_5") (pintype "unspecified"))
    )
    (net (code "94") (name "unconnected-(SEG2-DP-Pad5)") (class "Default")
      (node (ref "SEG2") (pin "5") (pinfunction "DP_5") (pintype "unspecified"))
    )
    (net (code "95") (name "unconnected-(SEG3-DP-Pad5)") (class "Default")
      (node (ref "SEG3") (pin "5") (pinfunction "DP_5") (pintype "unspecified"))
    )
    (net (code "96") (name "unconnected-(SEG4-DP-Pad5)") (class "Default")
      (node (ref "SEG4") (pin "5") (pinfunction "DP_5") (pintype "unspecified"))
    )
    (net (code "97") (name "unconnected-(SEG5-DP-Pad5)") (class "Default")
      (node (ref "SEG5") (pin "5") (pinfunction "DP_5") (pintype "unspecified"))
    )
    (net (code "98") (name "unconnected-(SEG6-DP-Pad5)") (class "Default")
      (node (ref "SEG6") (pin "5") (pinfunction "DP_5") (pintype "unspecified"))
    )
    (net (code "99") (name "unconnected-(U1-A-Pad3)") (class "Default")
      (node (ref "U1") (pin "3") (pinfunction "A_3") (pintype "unspecified"))
    )
    (net (code "100") (name "unconnected-(U1-B-Pad4)") (class "Default")
      (node (ref "U1") (pin "4") (pinfunction "B_4") (pintype "unspecified"))
    )
    (net (code "101") (name "unconnected-(U1-C-Pad5)") (class "Default")
      (node (ref "U1") (pin "5") (pinfunction "C_5") (pintype "unspecified"))
    )
    (net (code "102") (name "unconnected-(U1-D-Pad6)") (class "Default")
      (node (ref "U1") (pin "6") (pinfunction "D_6") (pintype "unspecified"))
    )
    (net (code "103") (name "unconnected-(U1-RCO-Pad15)") (class "Default")
      (node (ref "U1") (pin "15") (pinfunction "RCO_15") (pintype "unspecified"))
    )
    (net (code "104") (name "unconnected-(U4-A-Pad3)") (class "Default")
      (node (ref "U4") (pin "3") (pinfunction "A_3") (pintype "unspecified"))
    )
    (net (code "105") (name "unconnected-(U4-B-Pad4)") (class "Default")
      (node (ref "U4") (pin "4") (pinfunction "B_4") (pintype "unspecified"))
    )
    (net (code "106") (name "unconnected-(U4-C-Pad5)") (class "Default")
      (node (ref "U4") (pin "5") (pinfunction "C_5") (pintype "unspecified"))
    )
    (net (code "107") (name "unconnected-(U4-D-Pad6)") (class "Default")
      (node (ref "U4") (pin "6") (pinfunction "D_6") (pintype "unspecified"))
    )
    (net (code "108") (name "unconnected-(U4-LOAD-Pad9)") (class "Default")
      (node (ref "U4") (pin "9") (pinfunction "LOAD_9") (pintype "unspecified"))
    )
    (net (code "109") (name "unconnected-(U4-RCO-Pad15)") (class "Default")
      (node (ref "U4") (pin "15") (pinfunction "RCO_15") (pintype "unspecified"))
    )
    (net (code "110") (name "unconnected-(U5-A-Pad3)") (class "Default")
      (node (ref "U5") (pin "3") (pinfunction "A_3") (pintype "unspecified"))
    )
    (net (code "111") (name "unconnected-(U5-B-Pad4)") (class "Default")
      (node (ref "U5") (pin "4") (pinfunction "B_4") (pintype "unspecified"))
    )
    (net (code "112") (name "unconnected-(U5-C-Pad5)") (class "Default")
      (node (ref "U5") (pin "5") (pinfunction "C_5") (pintype "unspecified"))
    )
    (net (code "113") (name "unconnected-(U5-D-Pad6)") (class "Default")
      (node (ref "U5") (pin "6") (pinfunction "D_6") (pintype "unspecified"))
    )
    (net (code "114") (name "unconnected-(U5-RCO-Pad15)") (class "Default")
      (node (ref "U5") (pin "15") (pinfunction "RCO_15") (pintype "unspecified"))
    )
    (net (code "115") (name "unconnected-(U6-A-Pad3)") (class "Default")
      (node (ref "U6") (pin "3") (pinfunction "A_3") (pintype "unspecified"))
    )
    (net (code "116") (name "unconnected-(U6-B-Pad4)") (class "Default")
      (node (ref "U6") (pin "4") (pinfunction "B_4") (pintype "unspecified"))
    )
    (net (code "117") (name "unconnected-(U6-C-Pad5)") (class "Default")
      (node (ref "U6") (pin "5") (pinfunction "C_5") (pintype "unspecified"))
    )
    (net (code "118") (name "unconnected-(U6-D-Pad6)") (class "Default")
      (node (ref "U6") (pin "6") (pinfunction "D_6") (pintype "unspecified"))
    )
    (net (code "119") (name "unconnected-(U6-RCO-Pad15)") (class "Default")
      (node (ref "U6") (pin "15") (pinfunction "RCO_15") (pintype "unspecified"))
    )
    (net (code "120") (name "unconnected-(U7-A-Pad3)") (class "Default")
      (node (ref "U7") (pin "3") (pinfunction "A_3") (pintype "unspecified"))
    )
    (net (code "121") (name "unconnected-(U7-B-Pad4)") (class "Default")
      (node (ref "U7") (pin "4") (pinfunction "B_4") (pintype "unspecified"))
    )
    (net (code "122") (name "unconnected-(U7-C-Pad5)") (class "Default")
      (node (ref "U7") (pin "5") (pinfunction "C_5") (pintype "unspecified"))
    )
    (net (code "123") (name "unconnected-(U7-D-Pad6)") (class "Default")
      (node (ref "U7") (pin "6") (pinfunction "D_6") (pintype "unspecified"))
    )
    (net (code "124") (name "unconnected-(U7-RCO-Pad15)") (class "Default")
      (node (ref "U7") (pin "15") (pinfunction "RCO_15") (pintype "unspecified"))
    )
    (net (code "125") (name "unconnected-(U8-A-Pad3)") (class "Default")
      (node (ref "U8") (pin "3") (pinfunction "A_3") (pintype "unspecified"))
    )
    (net (code "126") (name "unconnected-(U8-B-Pad4)") (class "Default")
      (node (ref "U8") (pin "4") (pinfunction "B_4") (pintype "unspecified"))
    )
    (net (code "127") (name "unconnected-(U8-C-Pad5)") (class "Default")
      (node (ref "U8") (pin "5") (pinfunction "C_5") (pintype "unspecified"))
    )
    (net (code "128") (name "unconnected-(U8-D-Pad6)") (class "Default")
      (node (ref "U8") (pin "6") (pinfunction "D_6") (pintype "unspecified"))
    )
    (net (code "129") (name "unconnected-(U8-RCO-Pad15)") (class "Default")
      (node (ref "U8") (pin "15") (pinfunction "RCO_15") (pintype "unspecified"))
    )
    (net (code "130") (name "unconnected-(U10-4A-Pad9)") (class "Default")
      (node (ref "U10") (pin "9") (pinfunction "4A_9") (pintype "unspecified"))
    )
    (net (code "131") (name "unconnected-(U10-4Y-Pad8)") (class "Default")
      (node (ref "U10") (pin "8") (pinfunction "4Y_8") (pintype "unspecified"))
    )
    (net (code "132") (name "unconnected-(U10-5A-Pad11)") (class "Default")
      (node (ref "U10") (pin "11") (pinfunction "5A_11") (pintype "unspecified"))
    )
    (net (code "133") (name "unconnected-(U10-5Y-Pad10)") (class "Default")
      (node (ref "U10") (pin "10") (pinfunction "5Y_10") (pintype "unspecified"))
    )
    (net (code "134") (name "unconnected-(U10-6A-Pad13)") (class "Default")
      (node (ref "U10") (pin "13") (pinfunction "6A_13") (pintype "unspecified"))
    )
    (net (code "135") (name "unconnected-(U10-6Y-Pad12)") (class "Default")
      (node (ref "U10") (pin "12") (pinfunction "6Y_12") (pintype "unspecified"))
    )
    (net (code "136") (name "unconnected-(U17-3A-Pad9)") (class "Default")
      (node (ref "U17") (pin "9") (pinfunction "3A_9") (pintype "unspecified"))
    )
    (net (code "137") (name "unconnected-(U17-3B-Pad10)") (class "Default")
      (node (ref "U17") (pin "10") (pinfunction "3B_10") (pintype "unspecified"))
    )
    (net (code "138") (name "unconnected-(U17-3Y-Pad8)") (class "Default")
      (node (ref "U17") (pin "8") (pinfunction "3Y_8") (pintype "unspecified"))
    )
  )
)
